# Sheet.net
KiCad netlist of a schematic drawn in Altium Designer
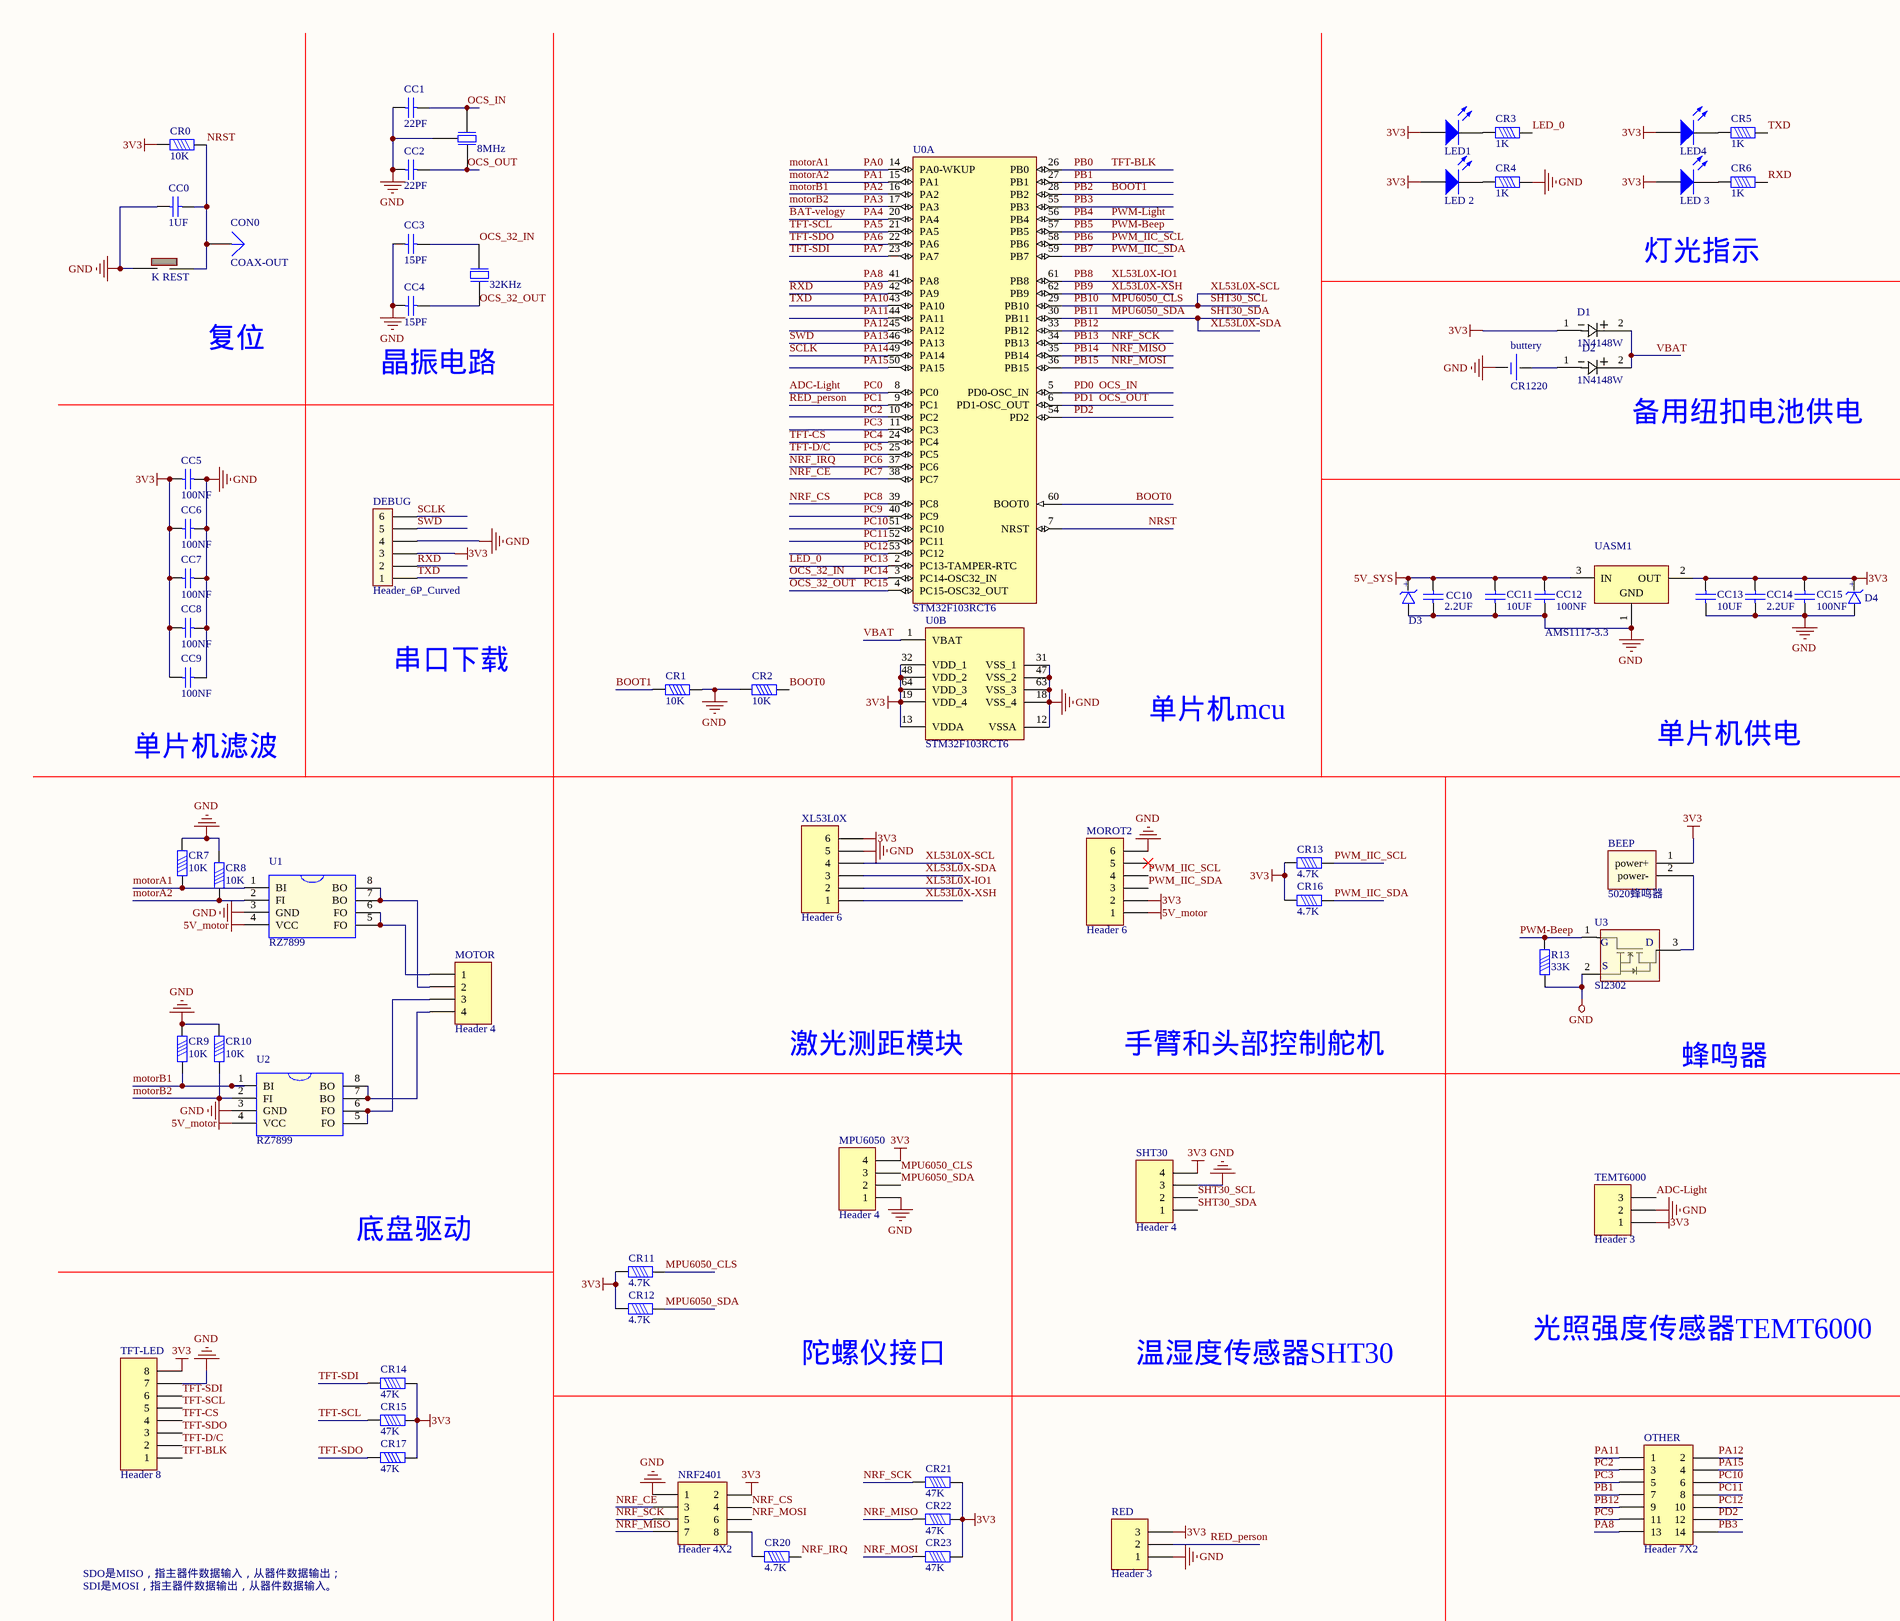
[diagram p0: Sheet.SchDoc, top left]
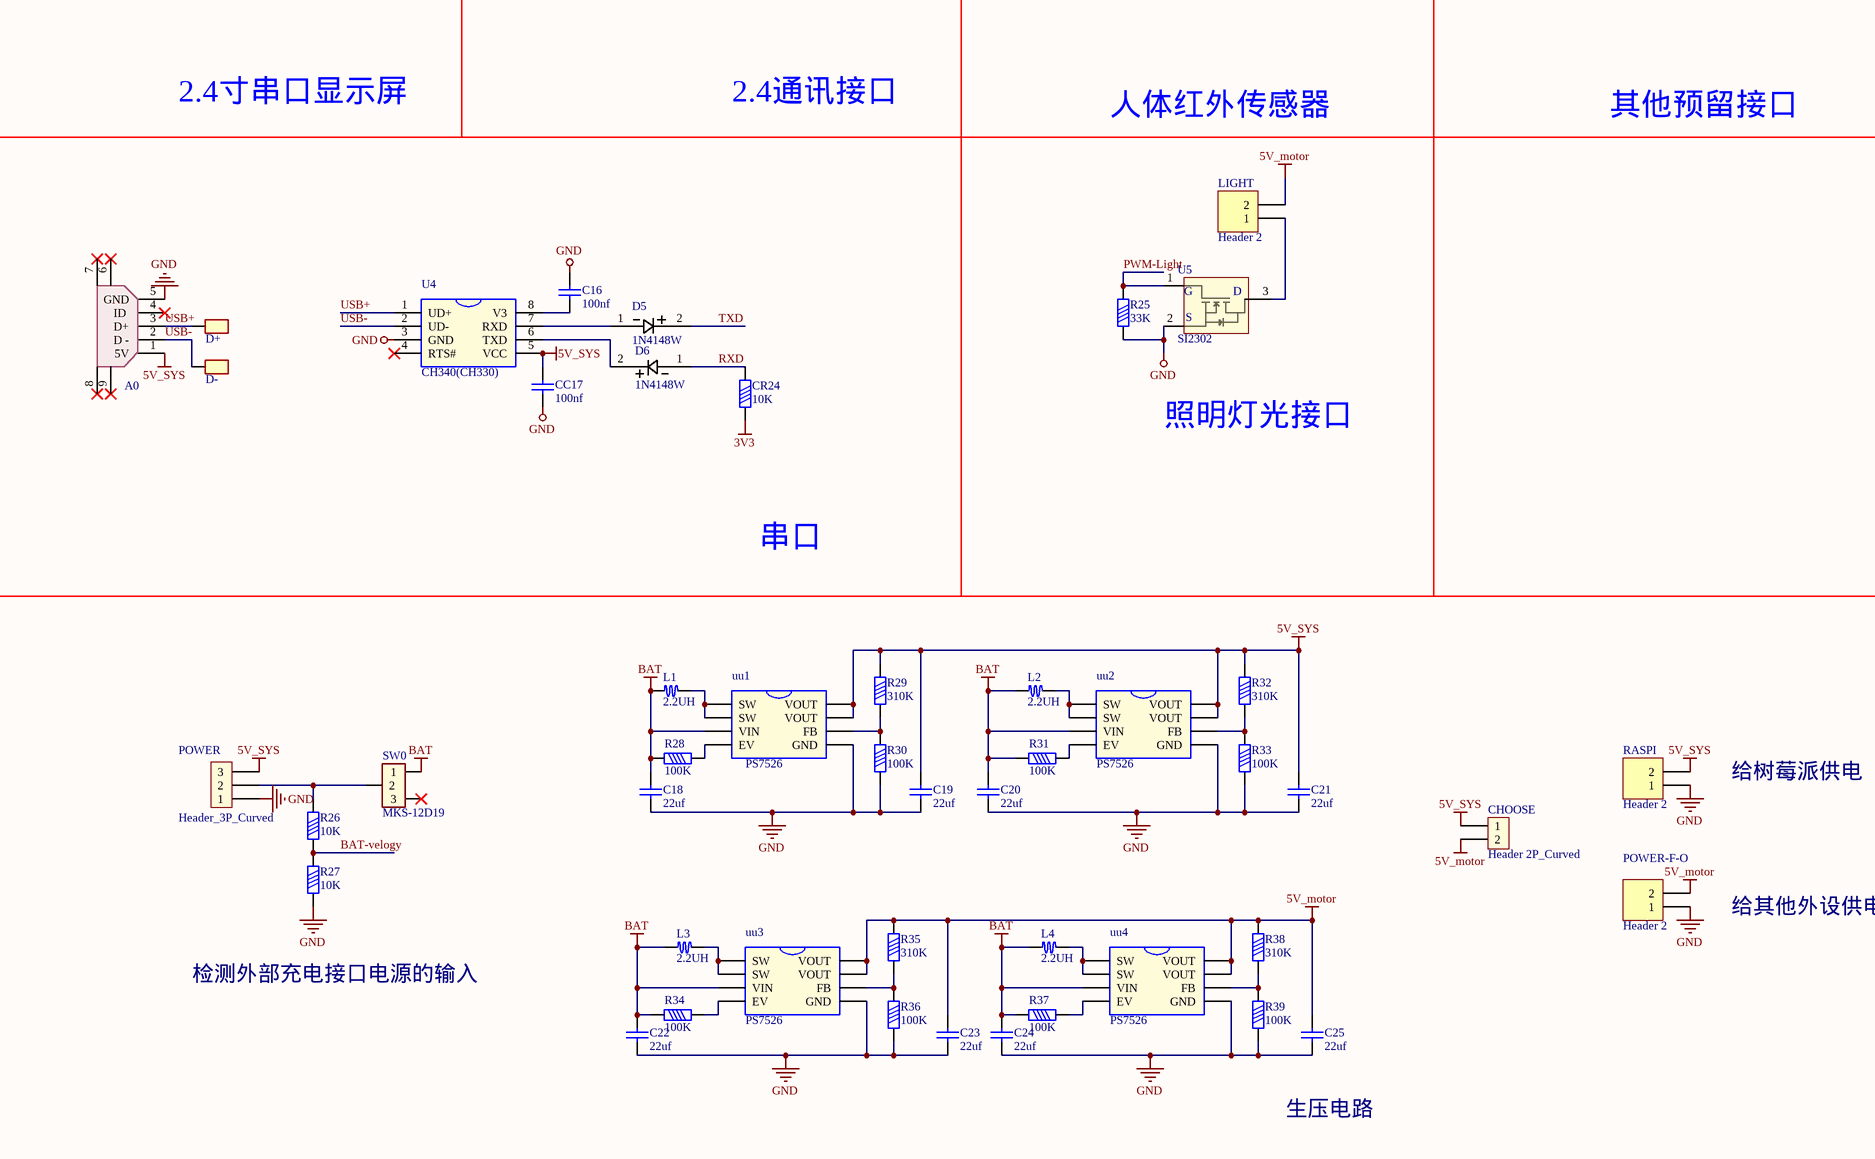
[diagram p1: Sheet.SchDoc, bottom left]

(export (version "E")
  (design (tool "Eeschema 10.0.6"))
  (components
    (comp (ref "8MHz")
      (value "XTAL 3225 8M")
      (footprint "T 3225")
      (libsource (lib "tianxiaohua_Schlib") (part "XTAL 3225 8M"))
    )
    (comp (ref "32KHz")
      (value "XTAL 3215 32.768kKHz")
      (footprint "T 3215")
      (libsource (lib "tianxiaohua_Schlib") (part "XTAL 3215 32.768kKHz"))
    )
    (comp (ref "A0")
      (value "Micro USB")
      (footprint "Micro USB")
      (libsource (lib "tianxiaohua_Schlib") (part "Micro USB"))
    )
    (comp (ref "BEEP")
      (value "5020蜂鸣器")
      (footprint "5020蜂鸣器")
      (description "蜂鸣器，贴片封装，长宽5.2mm")
      (libsource (lib "tianxiaohua_Schlib") (part "5020蜂鸣器"))
    )
    (comp (ref "buttery")
      (value "CR1220")
      (footprint "CR1220-buttery")
      (description "纽扣电池")
      (libsource (lib "tianxiaohua_Schlib") (part "CR1220"))
    )
    (comp (ref "C16")
      (value "100nf")
      (footprint "CC1608-0603")
      (description "Polarized Capacitor (Radial)")
      (fields (field (name "Comment") "Cap Chip 0603") (field (name "PUBLISHER") "Altium Limited"))
      (libsource (lib "EButterflyIntegratedLibrary") (part "Cap Chip 0603"))
    )
    (comp (ref "C18")
      (value "22uf")
      (footprint "CC2012-0805")
      (description "Polarized Capacitor (Radial)")
      (fields (field (name "Comment") "Cap Chip 0805") (field (name "PUBLISHER") "Altium Limited"))
      (libsource (lib "EButterflyIntegratedLibrary") (part "Cap Chip 0805"))
    )
    (comp (ref "C19")
      (value "22uf")
      (footprint "CC2012-0805")
      (description "Polarized Capacitor (Radial)")
      (fields (field (name "Comment") "Cap Chip 0805") (field (name "PUBLISHER") "Altium Limited"))
      (libsource (lib "EButterflyIntegratedLibrary") (part "Cap Chip 0805"))
    )
    (comp (ref "C20")
      (value "22uf")
      (footprint "CC2012-0805")
      (description "Polarized Capacitor (Radial)")
      (fields (field (name "Comment") "Cap Chip 0805") (field (name "PUBLISHER") "Altium Limited"))
      (libsource (lib "EButterflyIntegratedLibrary") (part "Cap Chip 0805"))
    )
    (comp (ref "C21")
      (value "22uf")
      (footprint "CC2012-0805")
      (description "Polarized Capacitor (Radial)")
      (fields (field (name "Comment") "Cap Chip 0805") (field (name "PUBLISHER") "Altium Limited"))
      (libsource (lib "EButterflyIntegratedLibrary") (part "Cap Chip 0805"))
    )
    (comp (ref "C22")
      (value "22uf")
      (footprint "CC2012-0805")
      (description "Polarized Capacitor (Radial)")
      (fields (field (name "Comment") "Cap Chip 0805") (field (name "PUBLISHER") "Altium Limited"))
      (libsource (lib "EButterflyIntegratedLibrary") (part "Cap Chip 0805"))
    )
    (comp (ref "C23")
      (value "22uf")
      (footprint "CC2012-0805")
      (description "Polarized Capacitor (Radial)")
      (fields (field (name "Comment") "Cap Chip 0805") (field (name "PUBLISHER") "Altium Limited"))
      (libsource (lib "EButterflyIntegratedLibrary") (part "Cap Chip 0805"))
    )
    (comp (ref "C24")
      (value "22uf")
      (footprint "CC2012-0805")
      (description "Polarized Capacitor (Radial)")
      (fields (field (name "Comment") "Cap Chip 0805") (field (name "PUBLISHER") "Altium Limited"))
      (libsource (lib "EButterflyIntegratedLibrary") (part "Cap Chip 0805"))
    )
    (comp (ref "C25")
      (value "22uf")
      (footprint "CC2012-0805")
      (description "Polarized Capacitor (Radial)")
      (fields (field (name "Comment") "Cap Chip 0805") (field (name "PUBLISHER") "Altium Limited"))
      (libsource (lib "EButterflyIntegratedLibrary") (part "Cap Chip 0805"))
    )
    (comp (ref "CC0")
      (value "1UF")
      (footprint "CC1608-0603")
      (description "Polarized Capacitor (Radial)")
      (fields (field (name "Comment") "Cap Chip 0603") (field (name "PUBLISHER") "Altium Limited"))
      (libsource (lib "EButterflyIntegratedLibrary") (part "Cap Chip 0603"))
    )
    (comp (ref "CC1")
      (value "22PF")
      (footprint "CC1608-0603")
      (description "Polarized Capacitor (Radial)")
      (fields (field (name "Comment") "Cap Chip 0603") (field (name "PUBLISHER") "Altium Limited"))
      (libsource (lib "EButterflyIntegratedLibrary") (part "Cap Chip 0603"))
    )
    (comp (ref "CC2")
      (value "22PF")
      (footprint "CC1608-0603")
      (description "Polarized Capacitor (Radial)")
      (fields (field (name "Comment") "Cap Chip 0603") (field (name "PUBLISHER") "Altium Limited"))
      (libsource (lib "EButterflyIntegratedLibrary") (part "Cap Chip 0603"))
    )
    (comp (ref "CC3")
      (value "15PF")
      (footprint "CC1608-0603")
      (description "Polarized Capacitor (Radial)")
      (fields (field (name "Comment") "Cap Chip 0603") (field (name "PUBLISHER") "Altium Limited"))
      (libsource (lib "EButterflyIntegratedLibrary") (part "Cap Chip 0603"))
    )
    (comp (ref "CC4")
      (value "15PF")
      (footprint "CC1608-0603")
      (description "Polarized Capacitor (Radial)")
      (fields (field (name "Comment") "Cap Chip 0603") (field (name "PUBLISHER") "Altium Limited"))
      (libsource (lib "EButterflyIntegratedLibrary") (part "Cap Chip 0603"))
    )
    (comp (ref "CC5")
      (value "100NF")
      (footprint "CC1608-0603")
      (description "Polarized Capacitor (Radial)")
      (fields (field (name "Comment") "Cap Chip 0603") (field (name "PUBLISHER") "Altium Limited"))
      (libsource (lib "EButterflyIntegratedLibrary") (part "Cap Chip 0603"))
    )
    (comp (ref "CC6")
      (value "100NF")
      (footprint "CC1608-0603")
      (description "Polarized Capacitor (Radial)")
      (fields (field (name "Comment") "Cap Chip 0603") (field (name "PUBLISHER") "Altium Limited"))
      (libsource (lib "EButterflyIntegratedLibrary") (part "Cap Chip 0603"))
    )
    (comp (ref "CC7")
      (value "100NF")
      (footprint "CC1608-0603")
      (description "Polarized Capacitor (Radial)")
      (fields (field (name "Comment") "Cap Chip 0603") (field (name "PUBLISHER") "Altium Limited"))
      (libsource (lib "EButterflyIntegratedLibrary") (part "Cap Chip 0603"))
    )
    (comp (ref "CC8")
      (value "100NF")
      (footprint "CC1608-0603")
      (description "Polarized Capacitor (Radial)")
      (fields (field (name "Comment") "Cap Chip 0603") (field (name "PUBLISHER") "Altium Limited"))
      (libsource (lib "EButterflyIntegratedLibrary") (part "Cap Chip 0603"))
    )
    (comp (ref "CC9")
      (value "100NF")
      (footprint "CC1608-0603")
      (description "Polarized Capacitor (Radial)")
      (fields (field (name "Comment") "Cap Chip 0603") (field (name "PUBLISHER") "Altium Limited"))
      (libsource (lib "EButterflyIntegratedLibrary") (part "Cap Chip 0603"))
    )
    (comp (ref "CC10")
      (value "2.2UF")
      (footprint "CC1608-0603")
      (description "Polarized Capacitor (Radial)")
      (fields (field (name "Comment") "Cap Chip 0603") (field (name "PUBLISHER") "Altium Limited"))
      (libsource (lib "EButterflyIntegratedLibrary") (part "Cap Chip 0603"))
    )
    (comp (ref "CC11")
      (value "10UF")
      (footprint "CC1608-0603")
      (description "Polarized Capacitor (Radial)")
      (fields (field (name "Comment") "Cap Chip 0603") (field (name "PUBLISHER") "Altium Limited"))
      (libsource (lib "EButterflyIntegratedLibrary") (part "Cap Chip 0603"))
    )
    (comp (ref "CC12")
      (value "100NF")
      (footprint "CC1608-0603")
      (description "Polarized Capacitor (Radial)")
      (fields (field (name "Comment") "Cap Chip 0603") (field (name "PUBLISHER") "Altium Limited"))
      (libsource (lib "EButterflyIntegratedLibrary") (part "Cap Chip 0603"))
    )
    (comp (ref "CC13")
      (value "10UF")
      (footprint "CC1608-0603")
      (description "Polarized Capacitor (Radial)")
      (fields (field (name "Comment") "Cap Chip 0603") (field (name "PUBLISHER") "Altium Limited"))
      (libsource (lib "EButterflyIntegratedLibrary") (part "Cap Chip 0603"))
    )
    (comp (ref "CC14")
      (value "2.2UF")
      (footprint "CC1608-0603")
      (description "Polarized Capacitor (Radial)")
      (fields (field (name "Comment") "Cap Chip 0603") (field (name "PUBLISHER") "Altium Limited"))
      (libsource (lib "EButterflyIntegratedLibrary") (part "Cap Chip 0603"))
    )
    (comp (ref "CC15")
      (value "100NF")
      (footprint "CC1608-0603")
      (description "Polarized Capacitor (Radial)")
      (fields (field (name "Comment") "Cap Chip 0603") (field (name "PUBLISHER") "Altium Limited"))
      (libsource (lib "EButterflyIntegratedLibrary") (part "Cap Chip 0603"))
    )
    (comp (ref "CC17")
      (value "100nf")
      (footprint "CC1608-0603")
      (description "Polarized Capacitor (Radial)")
      (fields (field (name "Comment") "Cap Chip 0603") (field (name "PUBLISHER") "Altium Limited"))
      (libsource (lib "EButterflyIntegratedLibrary") (part "Cap Chip 0603"))
    )
    (comp (ref "CHOOSE")
      (value "Header 2P_Curved")
      (footprint "Header_2_54_2PW")
      (description "弯的2P排针")
      (libsource (lib "tianxiaohua_Schlib") (part "Header 2P_Curved"))
    )
    (comp (ref "CON0")
      (value "COAX-OUT")
      (footprint "PIN1")
      (description "Coax-M Connector")
      (fields (field (name "PUBLISHER") "Altium Limited"))
      (libsource (lib "EButterflyIntegratedLibrary") (part "COAX-OUT"))
    )
    (comp (ref "CR0")
      (value "10K")
      (footprint "CR1608-0603")
      (description "Resistor")
      (fields (field (name "Comment") "Resistor Chip 0603") (field (name "PUBLISHER") "Altium Limited"))
      (libsource (lib "") (part "Resistor Chip 0603_1"))
    )
    (comp (ref "CR1")
      (value "10K")
      (footprint "CR1608-0603")
      (description "Resistor")
      (fields (field (name "Comment") "Resistor Chip 0603") (field (name "PUBLISHER") "Altium Limited"))
      (libsource (lib "") (part "Resistor Chip 0603_1"))
    )
    (comp (ref "CR2")
      (value "10K")
      (footprint "CR1608-0603")
      (description "Resistor")
      (fields (field (name "Comment") "Resistor Chip 0603") (field (name "PUBLISHER") "Altium Limited"))
      (libsource (lib "") (part "Resistor Chip 0603_1"))
    )
    (comp (ref "CR3")
      (value "1K")
      (footprint "CR1608-0603")
      (description "Resistor")
      (fields (field (name "Comment") "Resistor Chip 0603") (field (name "PUBLISHER") "Altium Limited"))
      (libsource (lib "") (part "Resistor Chip 0603_1"))
    )
    (comp (ref "CR4")
      (value "1K")
      (footprint "CR1608-0603")
      (description "Resistor")
      (fields (field (name "Comment") "Resistor Chip 0603") (field (name "PUBLISHER") "Altium Limited"))
      (libsource (lib "") (part "Resistor Chip 0603_1"))
    )
    (comp (ref "CR5")
      (value "1K")
      (footprint "CR1608-0603")
      (description "Resistor")
      (fields (field (name "Comment") "Resistor Chip 0603") (field (name "PUBLISHER") "Altium Limited"))
      (libsource (lib "") (part "Resistor Chip 0603_1"))
    )
    (comp (ref "CR6")
      (value "1K")
      (footprint "CR1608-0603")
      (description "Resistor")
      (fields (field (name "Comment") "Resistor Chip 0603") (field (name "PUBLISHER") "Altium Limited"))
      (libsource (lib "") (part "Resistor Chip 0603_1"))
    )
    (comp (ref "CR7")
      (value "10K")
      (footprint "CR1608-0603")
      (description "Resistor")
      (fields (field (name "Comment") "Resistor Chip 0603") (field (name "PUBLISHER") "Altium Limited"))
      (libsource (lib "") (part "Resistor Chip 0603_2"))
    )
    (comp (ref "CR8")
      (value "10K")
      (footprint "CR1608-0603")
      (description "Resistor")
      (fields (field (name "Comment") "Resistor Chip 0603") (field (name "PUBLISHER") "Altium Limited"))
      (libsource (lib "") (part "Resistor Chip 0603_2"))
    )
    (comp (ref "CR9")
      (value "10K")
      (footprint "CR1608-0603")
      (description "Resistor")
      (fields (field (name "Comment") "Resistor Chip 0603") (field (name "PUBLISHER") "Altium Limited"))
      (libsource (lib "EButterflyIntegratedLibrary") (part "Resistor Chip 0603"))
    )
    (comp (ref "CR10")
      (value "10K")
      (footprint "CR1608-0603")
      (description "Resistor")
      (fields (field (name "Comment") "Resistor Chip 0603") (field (name "PUBLISHER") "Altium Limited"))
      (libsource (lib "EButterflyIntegratedLibrary") (part "Resistor Chip 0603"))
    )
    (comp (ref "CR11")
      (value "4.7K")
      (footprint "CR1608-0603")
      (description "Resistor")
      (fields (field (name "Comment") "Resistor Chip 0603") (field (name "PUBLISHER") "Altium Limited"))
      (libsource (lib "") (part "Resistor Chip 0603_1"))
    )
    (comp (ref "CR12")
      (value "4.7K")
      (footprint "CR1608-0603")
      (description "Resistor")
      (fields (field (name "Comment") "Resistor Chip 0603") (field (name "PUBLISHER") "Altium Limited"))
      (libsource (lib "") (part "Resistor Chip 0603_1"))
    )
    (comp (ref "CR13")
      (value "4.7K")
      (footprint "CR1608-0603")
      (description "Resistor")
      (fields (field (name "Comment") "Resistor Chip 0603") (field (name "PUBLISHER") "Altium Limited"))
      (libsource (lib "") (part "Resistor Chip 0603_1"))
    )
    (comp (ref "CR14")
      (value "47K")
      (footprint "CR1608-0603")
      (description "Resistor")
      (fields (field (name "Comment") "Resistor Chip 0603") (field (name "PUBLISHER") "Altium Limited"))
      (libsource (lib "") (part "Resistor Chip 0603_1"))
    )
    (comp (ref "CR15")
      (value "47K")
      (footprint "CR1608-0603")
      (description "Resistor")
      (fields (field (name "Comment") "Resistor Chip 0603") (field (name "PUBLISHER") "Altium Limited"))
      (libsource (lib "") (part "Resistor Chip 0603_1"))
    )
    (comp (ref "CR16")
      (value "4.7K")
      (footprint "CR1608-0603")
      (description "Resistor")
      (fields (field (name "Comment") "Resistor Chip 0603") (field (name "PUBLISHER") "Altium Limited"))
      (libsource (lib "") (part "Resistor Chip 0603_1"))
    )
    (comp (ref "CR17")
      (value "47K")
      (footprint "CR1608-0603")
      (description "Resistor")
      (fields (field (name "Comment") "Resistor Chip 0603") (field (name "PUBLISHER") "Altium Limited"))
      (libsource (lib "") (part "Resistor Chip 0603_1"))
    )
    (comp (ref "CR20")
      (value "4.7K")
      (footprint "CR1608-0603")
      (description "Resistor")
      (fields (field (name "Comment") "Resistor Chip 0603") (field (name "PUBLISHER") "Altium Limited"))
      (libsource (lib "") (part "Resistor Chip 0603_1"))
    )
    (comp (ref "CR21")
      (value "47K")
      (footprint "CR1608-0603")
      (description "Resistor")
      (fields (field (name "Comment") "Resistor Chip 0603") (field (name "PUBLISHER") "Altium Limited"))
      (libsource (lib "") (part "Resistor Chip 0603_1"))
    )
    (comp (ref "CR22")
      (value "47K")
      (footprint "CR1608-0603")
      (description "Resistor")
      (fields (field (name "Comment") "Resistor Chip 0603") (field (name "PUBLISHER") "Altium Limited"))
      (libsource (lib "") (part "Resistor Chip 0603_1"))
    )
    (comp (ref "CR23")
      (value "47K")
      (footprint "CR1608-0603")
      (description "Resistor")
      (fields (field (name "Comment") "Resistor Chip 0603") (field (name "PUBLISHER") "Altium Limited"))
      (libsource (lib "") (part "Resistor Chip 0603_1"))
    )
    (comp (ref "CR24")
      (value "10K")
      (footprint "CR1608-0603")
      (description "Resistor")
      (fields (field (name "Comment") "Resistor Chip 0603") (field (name "PUBLISHER") "Altium Limited"))
      (libsource (lib "") (part "Resistor Chip 0603_2"))
    )
    (comp (ref "D+")
      (value "H0")
      (footprint "header 1")
      (libsource (lib "tianxiaohua_Schlib") (part "header 1"))
    )
    (comp (ref "D-")
      (value "H0")
      (footprint "header 1")
      (libsource (lib "tianxiaohua_Schlib") (part "header 1"))
    )
    (comp (ref "D1")
      (value "1N4148W")
      (footprint "SOD-123")
      (description "开关二极管 贴片 1N4148W 1206/SOD-123 丝印T4 150MA 75V")
      (libsource (lib "tianxiaohua_Schlib") (part "1N4148W"))
    )
    (comp (ref "D2")
      (value "1N4148W")
      (footprint "SOD-123")
      (description "开关二极管 贴片 1N4148W 1206/SOD-123 丝印T4 150MA 75V")
      (libsource (lib "tianxiaohua_Schlib") (part "1N4148W"))
    )
    (comp (ref "D3")
      (value "SMBJ3.3A")
      (footprint "DO214AA(SMB)")
      (description "3.3V稳压管，缓解瞬间电压冲击")
      (libsource (lib "tianxiaohua_Schlib") (part "SMBJ3.3A"))
    )
    (comp (ref "D4")
      (value "SMBJ3.3A")
      (footprint "DO214AA(SMB)")
      (description "3.3V稳压管，缓解瞬间电压冲击")
      (libsource (lib "tianxiaohua_Schlib") (part "SMBJ3.3A"))
    )
    (comp (ref "D5")
      (value "1N4148W")
      (footprint "SOD-123")
      (description "开关二极管 贴片 1N4148W 1206/SOD-123 丝印T4 150MA 75V")
      (libsource (lib "tianxiaohua_Schlib") (part "1N4148W"))
    )
    (comp (ref "D6")
      (value "1N4148W")
      (footprint "SOD-123")
      (description "开关二极管 贴片 1N4148W 1206/SOD-123 丝印T4 150MA 75V")
      (libsource (lib "tianxiaohua_Schlib") (part "1N4148W"))
    )
    (comp (ref "DEBUG")
      (value "Header_6P_Curved")
      (footprint "Header_2_54_6PW")
      (description "弯的6P排针")
      (libsource (lib "tianxiaohua_Schlib") (part "Header_6P_Curved"))
    )
    (comp (ref "K REST")
      (value "KEY 3*4")
      (footprint "KEY 3*4")
      (libsource (lib "tianxiaohua_Schlib") (part "KEY 3*4"))
    )
    (comp (ref "L1")
      (value "2.2UH")
      (footprint "Inductor-1040")
      (description "圆柱线圈的贴片电感")
      (libsource (lib "tianxiaohua_Schlib") (part "Inductor"))
    )
    (comp (ref "L2")
      (value "2.2UH")
      (footprint "Inductor-1040")
      (description "圆柱线圈的贴片电感")
      (libsource (lib "tianxiaohua_Schlib") (part "Inductor"))
    )
    (comp (ref "L3")
      (value "2.2UH")
      (footprint "Inductor-1040")
      (description "圆柱线圈的贴片电感")
      (libsource (lib "tianxiaohua_Schlib") (part "Inductor"))
    )
    (comp (ref "L4")
      (value "2.2UH")
      (footprint "Inductor-1040")
      (description "圆柱线圈的贴片电感")
      (libsource (lib "tianxiaohua_Schlib") (part "Inductor"))
    )
    (comp (ref "LED 2")
      (value "LED Chip")
      (footprint "CLED1608-0603")
      (description "Typical Chip LED")
      (fields (field (name "PUBLISHER") "Altium Limited"))
      (libsource (lib "EButterflyIntegratedLibrary") (part "LED Chip"))
    )
    (comp (ref "LED 3")
      (value "LED Chip")
      (footprint "CLED1608-0603")
      (description "Typical Chip LED")
      (fields (field (name "PUBLISHER") "Altium Limited"))
      (libsource (lib "EButterflyIntegratedLibrary") (part "LED Chip"))
    )
    (comp (ref "LED1")
      (value "LED Chip")
      (footprint "CLED1608-0603")
      (description "Typical Chip LED")
      (fields (field (name "PUBLISHER") "Altium Limited"))
      (libsource (lib "EButterflyIntegratedLibrary") (part "LED Chip"))
    )
    (comp (ref "LED4")
      (value "LED Chip")
      (footprint "CLED1608-0603")
      (description "Typical Chip LED")
      (fields (field (name "PUBLISHER") "Altium Limited"))
      (libsource (lib "EButterflyIntegratedLibrary") (part "LED Chip"))
    )
    (comp (ref "LIGHT")
      (value "Header 2")
      (footprint "HX2.54-2")
      (description "Header, 2-Pin")
      (fields (field (name "PUBLISHER") "Altium Limited"))
      (libsource (lib "EButterflyIntegratedLibrary") (part "Header 2"))
    )
    (comp (ref "MOROT2")
      (value "Header 6")
      (footprint "HX2.54-6")
      (description "Header, 6-Pin")
      (fields (field (name "PUBLISHER") "Altium Limited"))
      (libsource (lib "EButterflyIntegratedLibrary") (part "Header 6"))
    )
    (comp (ref "MOTOR")
      (value "Header 4")
      (footprint "HX2.54-4")
      (description "Header, 4-Pin")
      (fields (field (name "PUBLISHER") "Altium Limited"))
      (libsource (lib "") (part "Header 4_1"))
    )
    (comp (ref "MPU6050")
      (value "Header 4")
      (footprint "HX2.54-4")
      (description "Header, 4-Pin")
      (fields (field (name "PUBLISHER") "Altium Limited"))
      (libsource (lib "EButterflyIntegratedLibrary") (part "Header 4"))
    )
    (comp (ref "NRF2401")
      (value "Header 4X2")
      (footprint "HDR2X4")
      (description "Header, 4-Pin, Dual row")
      (fields (field (name "PUBLISHER") "Altium Limited"))
      (libsource (lib "EButterflyIntegratedLibrary") (part "Header 4X2"))
    )
    (comp (ref "OTHER")
      (value "Header 7X2")
      (footprint "HDR2X7")
      (description "Header, 7-Pin, Dual row")
      (fields (field (name "PUBLISHER") "Altium Limited"))
      (libsource (lib "EButterflyIntegratedLibrary") (part "Header 7X2"))
    )
    (comp (ref "POWER")
      (value "Header_3P_Curved")
      (footprint "Header_2_54_3PW")
      (description "弯的3P排针")
      (libsource (lib "tianxiaohua_Schlib") (part "Header_3P_Curved"))
    )
    (comp (ref "POWER-F-O")
      (value "Header 2")
      (footprint "HX2.54-2")
      (description "Header, 2-Pin")
      (fields (field (name "PUBLISHER") "Altium Limited"))
      (libsource (lib "EButterflyIntegratedLibrary") (part "Header 2"))
    )
    (comp (ref "R13")
      (value "33K")
      (footprint "CR1608-0603")
      (description "Resistor")
      (fields (field (name "Comment") "Resistor Chip 0603") (field (name "PUBLISHER") "Altium Limited"))
      (libsource (lib "") (part "Resistor Chip 0603_2"))
    )
    (comp (ref "R25")
      (value "33K")
      (footprint "CR1608-0603")
      (description "Resistor")
      (fields (field (name "Comment") "Resistor Chip 0603") (field (name "PUBLISHER") "Altium Limited"))
      (libsource (lib "") (part "Resistor Chip 0603_2"))
    )
    (comp (ref "R26")
      (value "10K")
      (footprint "CR1608-0603")
      (description "Resistor")
      (fields (field (name "Comment") "Resistor Chip 0603") (field (name "PUBLISHER") "Altium Limited"))
      (libsource (lib "") (part "Resistor Chip 0603_2"))
    )
    (comp (ref "R27")
      (value "10K")
      (footprint "CR1608-0603")
      (description "Resistor")
      (fields (field (name "Comment") "Resistor Chip 0603") (field (name "PUBLISHER") "Altium Limited"))
      (libsource (lib "EButterflyIntegratedLibrary") (part "Resistor Chip 0603"))
    )
    (comp (ref "R28")
      (value "100K")
      (footprint "CR1608-0603")
      (description "Resistor")
      (fields (field (name "Comment") "Resistor Chip 0603") (field (name "PUBLISHER") "Altium Limited"))
      (libsource (lib "") (part "Resistor Chip 0603_1"))
    )
    (comp (ref "R29")
      (value "310K")
      (footprint "CR1608-0603")
      (description "Resistor")
      (fields (field (name "Comment") "Resistor Chip 0603") (field (name "PUBLISHER") "Altium Limited"))
      (libsource (lib "EButterflyIntegratedLibrary") (part "Resistor Chip 0603"))
    )
    (comp (ref "R30")
      (value "100K")
      (footprint "CR1608-0603")
      (description "Resistor")
      (fields (field (name "Comment") "Resistor Chip 0603") (field (name "PUBLISHER") "Altium Limited"))
      (libsource (lib "EButterflyIntegratedLibrary") (part "Resistor Chip 0603"))
    )
    (comp (ref "R31")
      (value "100K")
      (footprint "CR1608-0603")
      (description "Resistor")
      (fields (field (name "Comment") "Resistor Chip 0603") (field (name "PUBLISHER") "Altium Limited"))
      (libsource (lib "") (part "Resistor Chip 0603_1"))
    )
    (comp (ref "R32")
      (value "310K")
      (footprint "CR1608-0603")
      (description "Resistor")
      (fields (field (name "Comment") "Resistor Chip 0603") (field (name "PUBLISHER") "Altium Limited"))
      (libsource (lib "EButterflyIntegratedLibrary") (part "Resistor Chip 0603"))
    )
    (comp (ref "R33")
      (value "100K")
      (footprint "CR1608-0603")
      (description "Resistor")
      (fields (field (name "Comment") "Resistor Chip 0603") (field (name "PUBLISHER") "Altium Limited"))
      (libsource (lib "EButterflyIntegratedLibrary") (part "Resistor Chip 0603"))
    )
    (comp (ref "R34")
      (value "100K")
      (footprint "CR1608-0603")
      (description "Resistor")
      (fields (field (name "Comment") "Resistor Chip 0603") (field (name "PUBLISHER") "Altium Limited"))
      (libsource (lib "") (part "Resistor Chip 0603_1"))
    )
    (comp (ref "R35")
      (value "310K")
      (footprint "CR1608-0603")
      (description "Resistor")
      (fields (field (name "Comment") "Resistor Chip 0603") (field (name "PUBLISHER") "Altium Limited"))
      (libsource (lib "EButterflyIntegratedLibrary") (part "Resistor Chip 0603"))
    )
    (comp (ref "R36")
      (value "100K")
      (footprint "CR1608-0603")
      (description "Resistor")
      (fields (field (name "Comment") "Resistor Chip 0603") (field (name "PUBLISHER") "Altium Limited"))
      (libsource (lib "EButterflyIntegratedLibrary") (part "Resistor Chip 0603"))
    )
    (comp (ref "R37")
      (value "100K")
      (footprint "CR1608-0603")
      (description "Resistor")
      (fields (field (name "Comment") "Resistor Chip 0603") (field (name "PUBLISHER") "Altium Limited"))
      (libsource (lib "") (part "Resistor Chip 0603_1"))
    )
    (comp (ref "R38")
      (value "310K")
      (footprint "CR1608-0603")
      (description "Resistor")
      (fields (field (name "Comment") "Resistor Chip 0603") (field (name "PUBLISHER") "Altium Limited"))
      (libsource (lib "EButterflyIntegratedLibrary") (part "Resistor Chip 0603"))
    )
    (comp (ref "R39")
      (value "100K")
      (footprint "CR1608-0603")
      (description "Resistor")
      (fields (field (name "Comment") "Resistor Chip 0603") (field (name "PUBLISHER") "Altium Limited"))
      (libsource (lib "EButterflyIntegratedLibrary") (part "Resistor Chip 0603"))
    )
    (comp (ref "RASPI")
      (value "Header 2")
      (footprint "HX2.54-2")
      (description "Header, 2-Pin")
      (fields (field (name "PUBLISHER") "Altium Limited"))
      (libsource (lib "EButterflyIntegratedLibrary") (part "Header 2"))
    )
    (comp (ref "RED")
      (value "Header 3")
      (footprint "HX2.54-3")
      (description "Header, 3-Pin")
      (fields (field (name "PUBLISHER") "Altium Limited"))
      (libsource (lib "EButterflyIntegratedLibrary") (part "Header 3"))
    )
    (comp (ref "SHT30")
      (value "Header 4")
      (footprint "HX2.54-4")
      (description "Header, 4-Pin")
      (fields (field (name "PUBLISHER") "Altium Limited"))
      (libsource (lib "EButterflyIntegratedLibrary") (part "Header 4"))
    )
    (comp (ref "SW0")
      (value "MKS-12D19")
      (footprint "SW  MKS 12D19")
      (libsource (lib "tianxiaohua_Schlib") (part "sw-MSK-12D19"))
    )
    (comp (ref "TEMT6000")
      (value "Header 3")
      (footprint "HX2.54-3")
      (description "Header, 3-Pin")
      (fields (field (name "PUBLISHER") "Altium Limited"))
      (libsource (lib "EButterflyIntegratedLibrary") (part "Header 3"))
    )
    (comp (ref "TFT-LED")
      (value "Header 8")
      (footprint "HX2.54-8")
      (description "Header, 8-Pin")
      (fields (field (name "PUBLISHER") "Altium Limited"))
      (libsource (lib "EButterflyIntegratedLibrary") (part "Header 8"))
    )
    (comp (ref "U0")
      (value "STM32F103RCT6")
      (footprint "STM-LQFP64_N")
      (libsource (lib "STMicroelectronics STM32 F1") (part "STM32F103RCT6"))
    )
    (comp (ref "U1")
      (value "RZ7899")
      (footprint "SOP8")
      (description "电机驱动:输入支持3V-25V，输出支持6A")
      (libsource (lib "tianxiaohua_Schlib") (part "RZ7899"))
    )
    (comp (ref "U2")
      (value "RZ7899")
      (footprint "SOP8")
      (description "电机驱动:输入支持3V-25V，输出支持6A")
      (libsource (lib "tianxiaohua_Schlib") (part "RZ7899"))
    )
    (comp (ref "U3")
      (value "SI2302")
      (footprint "SOT-23 SI2302")
      (description "NMOS场效应MOS管 SOT-23")
      (libsource (lib "tianxiaohua_Schlib") (part "SI2302"))
    )
    (comp (ref "U4")
      (value "CH340(CH330)")
      (footprint "SOP8")
      (description "USB转串口rs232的芯片，内置晶振")
      (libsource (lib "tianxiaohua_Schlib") (part "CH340(CH330)"))
    )
    (comp (ref "U5")
      (value "SI2302")
      (footprint "SOT-23 SI2302")
      (description "NMOS场效应MOS管 SOT-23")
      (libsource (lib "tianxiaohua_Schlib") (part "SI2302"))
    )
    (comp (ref "UASM1")
      (value "AMS1117-3.3")
      (footprint "SOT-223")
      (description "POSITIVE OUTPUT VOLTAGE")
      (libsource (lib "EButterflyIntegratedLibrary") (part "AMS1117"))
    )
    (comp (ref "uu1")
      (value "PS7526")
      (footprint "ESOP8")
      (libsource (lib "tianxiaohua_Schlib") (part "PS7526"))
    )
    (comp (ref "uu2")
      (value "PS7526")
      (footprint "ESOP8")
      (libsource (lib "tianxiaohua_Schlib") (part "PS7526"))
    )
    (comp (ref "uu3")
      (value "PS7526")
      (footprint "ESOP8")
      (libsource (lib "tianxiaohua_Schlib") (part "PS7526"))
    )
    (comp (ref "uu4")
      (value "PS7526")
      (footprint "ESOP8")
      (libsource (lib "tianxiaohua_Schlib") (part "PS7526"))
    )
    (comp (ref "XL53L0X")
      (value "Header 6")
      (footprint "HX2.54-6")
      (description "Header, 6-Pin")
      (fields (field (name "PUBLISHER") "Altium Limited"))
      (libsource (lib "EButterflyIntegratedLibrary") (part "Header 6"))
    )
  )
  (nets
    (net (code "1") (name "/ADC-Light") (class "Default")
      (node (ref "TEMT6000") (pin "3") (pinfunction "3_3") (pintype "passive"))
      (node (ref "U0") (pin "8") (pinfunction "PC0_8") (pintype "bidirectional"))
    )
    (net (code "2") (name "/BAT-velogy") (class "Default")
      (node (ref "R26") (pin "1") (pinfunction "1_1") (pintype "passive"))
      (node (ref "R27") (pin "1") (pinfunction "1_1") (pintype "passive"))
      (node (ref "U0") (pin "20") (pinfunction "PA4_20") (pintype "bidirectional"))
    )
    (net (code "3") (name "/BOOT0") (class "Default")
      (node (ref "CR2") (pin "2") (pinfunction "2_2") (pintype "passive"))
      (node (ref "U0") (pin "60") (pinfunction "BOOT0_60") (pintype "input"))
    )
    (net (code "4") (name "/BOOT1") (class "Default")
      (node (ref "CR1") (pin "1") (pinfunction "1_1") (pintype "passive"))
      (node (ref "U0") (pin "28") (pinfunction "PB2_28") (pintype "bidirectional"))
    )
    (net (code "5") (name "/LED_0") (class "Default")
      (node (ref "CR3") (pin "2") (pinfunction "2_2") (pintype "passive"))
      (node (ref "U0") (pin "2") (pinfunction "PC13-TAMPER-RTC_2") (pintype "bidirectional"))
    )
    (net (code "6") (name "/MPU6050_CLS") (class "Default")
      (node (ref "CR11") (pin "2") (pinfunction "2_2") (pintype "passive"))
      (node (ref "MPU6050") (pin "3") (pinfunction "3_3") (pintype "passive"))
      (node (ref "SHT30") (pin "2") (pinfunction "2_2") (pintype "passive"))
      (node (ref "U0") (pin "29") (pinfunction "PB10_29") (pintype "bidirectional"))
      (node (ref "XL53L0X") (pin "4") (pinfunction "4_4") (pintype "passive"))
    )
    (net (code "7") (name "/MPU6050_SDA") (class "Default")
      (node (ref "CR12") (pin "2") (pinfunction "2_2") (pintype "passive"))
      (node (ref "MPU6050") (pin "2") (pinfunction "2_2") (pintype "passive"))
      (node (ref "SHT30") (pin "1") (pinfunction "1_1") (pintype "passive"))
      (node (ref "U0") (pin "30") (pinfunction "PB11_30") (pintype "bidirectional"))
      (node (ref "XL53L0X") (pin "3") (pinfunction "3_3") (pintype "passive"))
    )
    (net (code "8") (name "/NRF_CE") (class "Default")
      (node (ref "NRF2401") (pin "3") (pinfunction "3_3") (pintype "passive"))
      (node (ref "U0") (pin "38") (pinfunction "PC7_38") (pintype "bidirectional"))
    )
    (net (code "9") (name "/NRF_CS") (class "Default")
      (node (ref "NRF2401") (pin "4") (pinfunction "4_4") (pintype "passive"))
      (node (ref "U0") (pin "39") (pinfunction "PC8_39") (pintype "bidirectional"))
    )
    (net (code "10") (name "/NRF_IRQ") (class "Default")
      (node (ref "CR20") (pin "2") (pinfunction "2_2") (pintype "passive"))
      (node (ref "U0") (pin "37") (pinfunction "PC6_37") (pintype "bidirectional"))
    )
    (net (code "11") (name "/NRF_MISO") (class "Default")
      (node (ref "CR22") (pin "1") (pinfunction "1_1") (pintype "passive"))
      (node (ref "NRF2401") (pin "7") (pinfunction "7_7") (pintype "passive"))
      (node (ref "U0") (pin "35") (pinfunction "PB14_35") (pintype "bidirectional"))
    )
    (net (code "12") (name "/NRF_MOSI") (class "Default")
      (node (ref "CR23") (pin "1") (pinfunction "1_1") (pintype "passive"))
      (node (ref "NRF2401") (pin "6") (pinfunction "6_6") (pintype "passive"))
      (node (ref "U0") (pin "36") (pinfunction "PB15_36") (pintype "bidirectional"))
    )
    (net (code "13") (name "/NRF_SCK") (class "Default")
      (node (ref "CR21") (pin "1") (pinfunction "1_1") (pintype "passive"))
      (node (ref "NRF2401") (pin "5") (pinfunction "5_5") (pintype "passive"))
      (node (ref "U0") (pin "34") (pinfunction "PB13_34") (pintype "bidirectional"))
    )
    (net (code "14") (name "/NRST") (class "Default")
      (node (ref "CC0") (pin "2") (pinfunction "2_2") (pintype "passive"))
      (node (ref "CON0") (pin "1") (pinfunction "A_1") (pintype "passive"))
      (node (ref "CR0") (pin "2") (pinfunction "2_2") (pintype "passive"))
      (node (ref "K REST") (pin "2") (pinfunction "2_2") (pintype "passive"))
      (node (ref "U0") (pin "7") (pinfunction "NRST_7") (pintype "bidirectional"))
    )
    (net (code "15") (name "/OCS_32_IN") (class "Default")
      (node (ref "32KHz") (pin "2") (pinfunction "OSC2_2") (pintype "passive"))
      (node (ref "CC3") (pin "2") (pinfunction "2_2") (pintype "passive"))
      (node (ref "U0") (pin "3") (pinfunction "PC14-OSC32_IN_3") (pintype "bidirectional"))
    )
    (net (code "16") (name "/OCS_32_OUT") (class "Default")
      (node (ref "32KHz") (pin "1") (pinfunction "OSC1_1") (pintype "passive"))
      (node (ref "CC4") (pin "2") (pinfunction "2_2") (pintype "passive"))
      (node (ref "U0") (pin "4") (pinfunction "PC15-OSC32_OUT_4") (pintype "bidirectional"))
    )
    (net (code "17") (name "/OCS_IN") (class "Default")
      (node (ref "8MHz") (pin "1") (pinfunction "OSC1_1") (pintype "passive"))
      (node (ref "CC1") (pin "2") (pinfunction "2_2") (pintype "passive"))
      (node (ref "U0") (pin "5") (pinfunction "PD0-OSC_IN_5") (pintype "bidirectional"))
    )
    (net (code "18") (name "/OCS_OUT") (class "Default")
      (node (ref "8MHz") (pin "2") (pinfunction "OSC2_2") (pintype "passive"))
      (node (ref "CC2") (pin "2") (pinfunction "2_2") (pintype "passive"))
      (node (ref "U0") (pin "6") (pinfunction "PD1-OSC_OUT_6") (pintype "bidirectional"))
    )
    (net (code "19") (name "/PA0") (class "Default")
      (node (ref "CR7") (pin "1") (pinfunction "1_1") (pintype "passive"))
      (node (ref "U0") (pin "14") (pinfunction "PA0-WKUP_14") (pintype "bidirectional"))
      (node (ref "U1") (pin "1") (pinfunction "BI_1") (pintype "passive"))
    )
    (net (code "20") (name "/PA1") (class "Default")
      (node (ref "CR8") (pin "1") (pinfunction "1_1") (pintype "passive"))
      (node (ref "U0") (pin "15") (pinfunction "PA1_15") (pintype "bidirectional"))
      (node (ref "U1") (pin "2") (pinfunction "FI_2") (pintype "passive"))
    )
    (net (code "21") (name "/PA2") (class "Default")
      (node (ref "CR9") (pin "2") (pinfunction "2_2") (pintype "passive"))
      (node (ref "U0") (pin "16") (pinfunction "PA2_16") (pintype "bidirectional"))
      (node (ref "U2") (pin "1") (pinfunction "BI_1") (pintype "passive"))
    )
    (net (code "22") (name "/PA3") (class "Default")
      (node (ref "CR10") (pin "2") (pinfunction "2_2") (pintype "passive"))
      (node (ref "U0") (pin "17") (pinfunction "PA3_17") (pintype "bidirectional"))
      (node (ref "U2") (pin "2") (pinfunction "FI_2") (pintype "passive"))
    )
    (net (code "23") (name "/PA5") (class "Default")
      (node (ref "CR15") (pin "1") (pinfunction "1_1") (pintype "passive"))
      (node (ref "TFT-LED") (pin "5") (pinfunction "5_5") (pintype "passive"))
      (node (ref "U0") (pin "21") (pinfunction "PA5_21") (pintype "bidirectional"))
    )
    (net (code "24") (name "/PA6") (class "Default")
      (node (ref "CR17") (pin "1") (pinfunction "1_1") (pintype "passive"))
      (node (ref "TFT-LED") (pin "3") (pinfunction "3_3") (pintype "passive"))
      (node (ref "U0") (pin "22") (pinfunction "PA6_22") (pintype "bidirectional"))
    )
    (net (code "25") (name "/PA7") (class "Default")
      (node (ref "CR14") (pin "1") (pinfunction "1_1") (pintype "passive"))
      (node (ref "TFT-LED") (pin "6") (pinfunction "6_6") (pintype "passive"))
      (node (ref "U0") (pin "23") (pinfunction "PA7_23") (pintype "bidirectional"))
    )
    (net (code "26") (name "/PA8") (class "Default")
      (node (ref "OTHER") (pin "13") (pinfunction "13_13") (pintype "passive"))
      (node (ref "U0") (pin "41") (pinfunction "PA8_41") (pintype "bidirectional"))
    )
    (net (code "27") (name "/PA9") (class "Default")
      (node (ref "CR24") (pin "2") (pinfunction "2_2") (pintype "passive"))
      (node (ref "CR6") (pin "2") (pinfunction "2_2") (pintype "passive"))
      (node (ref "D6") (pin "1") (pinfunction "1_1") (pintype "passive"))
      (node (ref "DEBUG") (pin "2") (pinfunction "2_2") (pintype "passive"))
      (node (ref "U0") (pin "42") (pinfunction "PA9_42") (pintype "bidirectional"))
    )
    (net (code "28") (name "/PA10") (class "Default")
      (node (ref "CR5") (pin "2") (pinfunction "2_2") (pintype "passive"))
      (node (ref "D5") (pin "2") (pinfunction "2_2") (pintype "passive"))
      (node (ref "DEBUG") (pin "1") (pinfunction "1_1") (pintype "passive"))
      (node (ref "U0") (pin "43") (pinfunction "PA10_43") (pintype "bidirectional"))
    )
    (net (code "29") (name "/PA11") (class "Default")
      (node (ref "OTHER") (pin "1") (pinfunction "1_1") (pintype "passive"))
      (node (ref "U0") (pin "44") (pinfunction "PA11_44") (pintype "bidirectional"))
    )
    (net (code "30") (name "/PA12") (class "Default")
      (node (ref "OTHER") (pin "2") (pinfunction "2_2") (pintype "passive"))
      (node (ref "U0") (pin "45") (pinfunction "PA12_45") (pintype "bidirectional"))
    )
    (net (code "31") (name "/PA13") (class "Default")
      (node (ref "DEBUG") (pin "5") (pinfunction "5_5") (pintype "passive"))
      (node (ref "U0") (pin "46") (pinfunction "PA13_46") (pintype "bidirectional"))
    )
    (net (code "32") (name "/PA14") (class "Default")
      (node (ref "DEBUG") (pin "6") (pinfunction "6_6") (pintype "passive"))
      (node (ref "U0") (pin "49") (pinfunction "PA14_49") (pintype "bidirectional"))
    )
    (net (code "33") (name "/PA15") (class "Default")
      (node (ref "OTHER") (pin "4") (pinfunction "4_4") (pintype "passive"))
      (node (ref "U0") (pin "50") (pinfunction "PA15_50") (pintype "bidirectional"))
    )
    (net (code "34") (name "/PB0") (class "Default")
      (node (ref "TFT-LED") (pin "1") (pinfunction "1_1") (pintype "passive"))
      (node (ref "U0") (pin "26") (pinfunction "PB0_26") (pintype "bidirectional"))
    )
    (net (code "35") (name "/PB1") (class "Default")
      (node (ref "OTHER") (pin "7") (pinfunction "7_7") (pintype "passive"))
      (node (ref "U0") (pin "27") (pinfunction "PB1_27") (pintype "bidirectional"))
    )
    (net (code "36") (name "/PB3") (class "Default")
      (node (ref "OTHER") (pin "14") (pinfunction "14_14") (pintype "passive"))
      (node (ref "U0") (pin "55") (pinfunction "PB3_55") (pintype "bidirectional"))
    )
    (net (code "37") (name "/PB4") (class "Default")
      (node (ref "R25") (pin "2") (pinfunction "2_2") (pintype "passive"))
      (node (ref "U0") (pin "56") (pinfunction "PB4_56") (pintype "bidirectional"))
      (node (ref "U5") (pin "1") (pinfunction "GATE_1") (pintype "passive"))
    )
    (net (code "38") (name "/PB5") (class "Default")
      (node (ref "R13") (pin "2") (pinfunction "2_2") (pintype "passive"))
      (node (ref "U0") (pin "57") (pinfunction "PB5_57") (pintype "bidirectional"))
      (node (ref "U3") (pin "1") (pinfunction "GATE_1") (pintype "passive"))
    )
    (net (code "39") (name "/PB6") (class "Default")
      (node (ref "CR13") (pin "2") (pinfunction "2_2") (pintype "passive"))
      (node (ref "MOROT2") (pin "4") (pinfunction "4_4") (pintype "passive"))
      (node (ref "U0") (pin "58") (pinfunction "PB6_58") (pintype "bidirectional"))
    )
    (net (code "40") (name "/PB7") (class "Default")
      (node (ref "CR16") (pin "2") (pinfunction "2_2") (pintype "passive"))
      (node (ref "MOROT2") (pin "3") (pinfunction "3_3") (pintype "passive"))
      (node (ref "U0") (pin "59") (pinfunction "PB7_59") (pintype "bidirectional"))
    )
    (net (code "41") (name "/PB8") (class "Default")
      (node (ref "U0") (pin "61") (pinfunction "PB8_61") (pintype "bidirectional"))
      (node (ref "XL53L0X") (pin "2") (pinfunction "2_2") (pintype "passive"))
    )
    (net (code "42") (name "/PB9") (class "Default")
      (node (ref "U0") (pin "62") (pinfunction "PB9_62") (pintype "bidirectional"))
      (node (ref "XL53L0X") (pin "1") (pinfunction "1_1") (pintype "passive"))
    )
    (net (code "43") (name "/PB12") (class "Default")
      (node (ref "OTHER") (pin "9") (pinfunction "9_9") (pintype "passive"))
      (node (ref "U0") (pin "33") (pinfunction "PB12_33") (pintype "bidirectional"))
    )
    (net (code "44") (name "/PC1") (class "Default")
      (node (ref "RED") (pin "2") (pinfunction "2_2") (pintype "passive"))
      (node (ref "U0") (pin "9") (pinfunction "PC1_9") (pintype "bidirectional"))
    )
    (net (code "45") (name "/PC2") (class "Default")
      (node (ref "OTHER") (pin "3") (pinfunction "3_3") (pintype "passive"))
      (node (ref "U0") (pin "10") (pinfunction "PC2_10") (pintype "bidirectional"))
    )
    (net (code "46") (name "/PC3") (class "Default")
      (node (ref "OTHER") (pin "5") (pinfunction "5_5") (pintype "passive"))
      (node (ref "U0") (pin "11") (pinfunction "PC3_11") (pintype "bidirectional"))
    )
    (net (code "47") (name "/PC4") (class "Default")
      (node (ref "TFT-LED") (pin "4") (pinfunction "4_4") (pintype "passive"))
      (node (ref "U0") (pin "24") (pinfunction "PC4_24") (pintype "bidirectional"))
    )
    (net (code "48") (name "/PC5") (class "Default")
      (node (ref "TFT-LED") (pin "2") (pinfunction "2_2") (pintype "passive"))
      (node (ref "U0") (pin "25") (pinfunction "PC5_25") (pintype "bidirectional"))
    )
    (net (code "49") (name "/PC9") (class "Default")
      (node (ref "OTHER") (pin "11") (pinfunction "11_11") (pintype "passive"))
      (node (ref "U0") (pin "40") (pinfunction "PC9_40") (pintype "bidirectional"))
    )
    (net (code "50") (name "/PC10") (class "Default")
      (node (ref "OTHER") (pin "6") (pinfunction "6_6") (pintype "passive"))
      (node (ref "U0") (pin "51") (pinfunction "PC10_51") (pintype "bidirectional"))
    )
    (net (code "51") (name "/PC11") (class "Default")
      (node (ref "OTHER") (pin "8") (pinfunction "8_8") (pintype "passive"))
      (node (ref "U0") (pin "52") (pinfunction "PC11_52") (pintype "bidirectional"))
    )
    (net (code "52") (name "/PC12") (class "Default")
      (node (ref "OTHER") (pin "10") (pinfunction "10_10") (pintype "passive"))
      (node (ref "U0") (pin "53") (pinfunction "PC12_53") (pintype "bidirectional"))
    )
    (net (code "53") (name "/PD2") (class "Default")
      (node (ref "OTHER") (pin "12") (pinfunction "12_12") (pintype "passive"))
      (node (ref "U0") (pin "54") (pinfunction "PD2_54") (pintype "bidirectional"))
    )
    (net (code "54") (name "/USB+") (class "Default")
      (node (ref "A0") (pin "3") (pinfunction "D+_3") (pintype "passive"))
      (node (ref "D+") (pin "1") (pinfunction "1_1") (pintype "passive"))
      (node (ref "U4") (pin "1") (pinfunction "UD+_1") (pintype "passive"))
    )
    (net (code "55") (name "/USB-") (class "Default")
      (node (ref "A0") (pin "2") (pinfunction "D_-_2") (pintype "passive"))
      (node (ref "D-") (pin "1") (pinfunction "1_1") (pintype "passive"))
      (node (ref "U4") (pin "2") (pinfunction "UD-_2") (pintype "passive"))
    )
    (net (code "56") (name "/VBAT") (class "Default")
      (node (ref "D1") (pin "2") (pinfunction "2_2") (pintype "passive"))
      (node (ref "D2") (pin "2") (pinfunction "2_2") (pintype "passive"))
      (node (ref "U0") (pin "1") (pinfunction "VBAT_1") (pintype "power_in"))
    )
    (net (code "57") (name "3V3") (class "Default")
      (node (ref "BEEP") (pin "1") (pinfunction "power+_1") (pintype "passive"))
      (node (ref "CC13") (pin "2") (pinfunction "2_2") (pintype "passive"))
      (node (ref "CC14") (pin "2") (pinfunction "2_2") (pintype "passive"))
      (node (ref "CC15") (pin "2") (pinfunction "2_2") (pintype "passive"))
      (node (ref "CC5") (pin "1") (pinfunction "1_1") (pintype "passive"))
      (node (ref "CC6") (pin "1") (pinfunction "1_1") (pintype "passive"))
      (node (ref "CC7") (pin "1") (pinfunction "1_1") (pintype "passive"))
      (node (ref "CC8") (pin "1") (pinfunction "1_1") (pintype "passive"))
      (node (ref "CC9") (pin "1") (pinfunction "1_1") (pintype "passive"))
      (node (ref "CR0") (pin "1") (pinfunction "1_1") (pintype "passive"))
      (node (ref "CR11") (pin "1") (pinfunction "1_1") (pintype "passive"))
      (node (ref "CR12") (pin "1") (pinfunction "1_1") (pintype "passive"))
      (node (ref "CR13") (pin "1") (pinfunction "1_1") (pintype "passive"))
      (node (ref "CR14") (pin "2") (pinfunction "2_2") (pintype "passive"))
      (node (ref "CR15") (pin "2") (pinfunction "2_2") (pintype "passive"))
      (node (ref "CR16") (pin "1") (pinfunction "1_1") (pintype "passive"))
      (node (ref "CR17") (pin "2") (pinfunction "2_2") (pintype "passive"))
      (node (ref "CR21") (pin "2") (pinfunction "2_2") (pintype "passive"))
      (node (ref "CR22") (pin "2") (pinfunction "2_2") (pintype "passive"))
      (node (ref "CR23") (pin "2") (pinfunction "2_2") (pintype "passive"))
      (node (ref "CR24") (pin "1") (pinfunction "1_1") (pintype "passive"))
      (node (ref "D1") (pin "1") (pinfunction "1_1") (pintype "passive"))
      (node (ref "D4") (pin "1") (pinfunction "1_1") (pintype "passive"))
      (node (ref "DEBUG") (pin "3") (pinfunction "3_3") (pintype "passive"))
      (node (ref "LED 2") (pin "1") (pinfunction "A_1") (pintype "passive"))
      (node (ref "LED 3") (pin "1") (pinfunction "A_1") (pintype "passive"))
      (node (ref "LED1") (pin "1") (pinfunction "A_1") (pintype "passive"))
      (node (ref "LED4") (pin "1") (pinfunction "A_1") (pintype "passive"))
      (node (ref "MOROT2") (pin "2") (pinfunction "2_2") (pintype "passive"))
      (node (ref "MPU6050") (pin "4") (pinfunction "4_4") (pintype "passive"))
      (node (ref "NRF2401") (pin "2") (pinfunction "2_2") (pintype "passive"))
      (node (ref "RED") (pin "3") (pinfunction "3_3") (pintype "passive"))
      (node (ref "SHT30") (pin "4") (pinfunction "4_4") (pintype "passive"))
      (node (ref "TEMT6000") (pin "1") (pinfunction "1_1") (pintype "passive"))
      (node (ref "TFT-LED") (pin "8") (pinfunction "8_8") (pintype "passive"))
      (node (ref "U0") (pin "13") (pinfunction "VDDA_13") (pintype "power_in"))
      (node (ref "U0") (pin "19") (pinfunction "VDD_4_19") (pintype "power_in"))
      (node (ref "U0") (pin "32") (pinfunction "VDD_1_32") (pintype "power_in"))
      (node (ref "U0") (pin "48") (pinfunction "VDD_2_48") (pintype "power_in"))
      (node (ref "U0") (pin "64") (pinfunction "VDD_3_64") (pintype "power_in"))
      (node (ref "UASM1") (pin "2") (pinfunction "OUT_2") (pintype "power_in"))
      (node (ref "XL53L0X") (pin "6") (pinfunction "6_6") (pintype "passive"))
    )
    (net (code "58") (name "5V_SYS") (class "Default")
      (node (ref "A0") (pin "1") (pinfunction "5V_1") (pintype "passive"))
      (node (ref "C19") (pin "1") (pinfunction "1_1") (pintype "passive"))
      (node (ref "C21") (pin "1") (pinfunction "1_1") (pintype "passive"))
      (node (ref "CC10") (pin "2") (pinfunction "2_2") (pintype "passive"))
      (node (ref "CC11") (pin "2") (pinfunction "2_2") (pintype "passive"))
      (node (ref "CC12") (pin "2") (pinfunction "2_2") (pintype "passive"))
      (node (ref "CC17") (pin "2") (pinfunction "2_2") (pintype "passive"))
      (node (ref "CHOOSE") (pin "1") (pinfunction "1_1") (pintype "passive"))
      (node (ref "D3") (pin "1") (pinfunction "1_1") (pintype "passive"))
      (node (ref "POWER") (pin "3") (pinfunction "3_3") (pintype "passive"))
      (node (ref "R29") (pin "1") (pinfunction "1_1") (pintype "passive"))
      (node (ref "R32") (pin "1") (pinfunction "1_1") (pintype "passive"))
      (node (ref "RASPI") (pin "2") (pinfunction "2_2") (pintype "passive"))
      (node (ref "U4") (pin "5") (pinfunction "VCC_5") (pintype "passive"))
      (node (ref "UASM1") (pin "3") (pinfunction "IN_3") (pintype "power_in"))
      (node (ref "uu1") (pin "7") (pinfunction "VOUT_7") (pintype "passive"))
      (node (ref "uu1") (pin "8") (pinfunction "VOUT_8") (pintype "passive"))
      (node (ref "uu2") (pin "7") (pinfunction "VOUT_7") (pintype "passive"))
      (node (ref "uu2") (pin "8") (pinfunction "VOUT_8") (pintype "passive"))
    )
    (net (code "59") (name "5V_motor") (class "Default")
      (node (ref "C23") (pin "1") (pinfunction "1_1") (pintype "passive"))
      (node (ref "C25") (pin "1") (pinfunction "1_1") (pintype "passive"))
      (node (ref "CHOOSE") (pin "2") (pinfunction "2_2") (pintype "passive"))
      (node (ref "LIGHT") (pin "2") (pinfunction "2_2") (pintype "passive"))
      (node (ref "MOROT2") (pin "1") (pinfunction "1_1") (pintype "passive"))
      (node (ref "POWER-F-O") (pin "2") (pinfunction "2_2") (pintype "passive"))
      (node (ref "R35") (pin "1") (pinfunction "1_1") (pintype "passive"))
      (node (ref "R38") (pin "1") (pinfunction "1_1") (pintype "passive"))
      (node (ref "U1") (pin "4") (pinfunction "VCC_4") (pintype "passive"))
      (node (ref "U2") (pin "4") (pinfunction "VCC_4") (pintype "passive"))
      (node (ref "uu3") (pin "7") (pinfunction "VOUT_7") (pintype "passive"))
      (node (ref "uu3") (pin "8") (pinfunction "VOUT_8") (pintype "passive"))
      (node (ref "uu4") (pin "7") (pinfunction "VOUT_7") (pintype "passive"))
      (node (ref "uu4") (pin "8") (pinfunction "VOUT_8") (pintype "passive"))
    )
    (net (code "60") (name "BAT") (class "Default")
      (node (ref "C18") (pin "1") (pinfunction "1_1") (pintype "passive"))
      (node (ref "C20") (pin "1") (pinfunction "1_1") (pintype "passive"))
      (node (ref "C22") (pin "1") (pinfunction "1_1") (pintype "passive"))
      (node (ref "C24") (pin "1") (pinfunction "1_1") (pintype "passive"))
      (node (ref "L1") (pin "1") (pinfunction "1_1") (pintype "passive"))
      (node (ref "L2") (pin "1") (pinfunction "1_1") (pintype "passive"))
      (node (ref "L3") (pin "1") (pinfunction "1_1") (pintype "passive"))
      (node (ref "L4") (pin "1") (pinfunction "1_1") (pintype "passive"))
      (node (ref "R28") (pin "1") (pinfunction "1_1") (pintype "passive"))
      (node (ref "R31") (pin "1") (pinfunction "1_1") (pintype "passive"))
      (node (ref "R34") (pin "1") (pinfunction "1_1") (pintype "passive"))
      (node (ref "R37") (pin "1") (pinfunction "1_1") (pintype "passive"))
      (node (ref "SW0") (pin "1") (pinfunction "1_1") (pintype "passive"))
      (node (ref "uu1") (pin "3") (pinfunction "VIN_3") (pintype "passive"))
      (node (ref "uu2") (pin "3") (pinfunction "VIN_3") (pintype "passive"))
      (node (ref "uu3") (pin "3") (pinfunction "VIN_3") (pintype "passive"))
      (node (ref "uu4") (pin "3") (pinfunction "VIN_3") (pintype "passive"))
    )
    (net (code "61") (name "GND") (class "Default")
      (node (ref "8MHz") (pin "3") (pinfunction "GND_3") (pintype "passive"))
      (node (ref "A0") (pin "5") (pinfunction "GND_5") (pintype "passive"))
      (node (ref "C16") (pin "1") (pinfunction "1_1") (pintype "passive"))
      (node (ref "C18") (pin "2") (pinfunction "2_2") (pintype "passive"))
      (node (ref "C19") (pin "2") (pinfunction "2_2") (pintype "passive"))
      (node (ref "C20") (pin "2") (pinfunction "2_2") (pintype "passive"))
      (node (ref "C21") (pin "2") (pinfunction "2_2") (pintype "passive"))
      (node (ref "C22") (pin "2") (pinfunction "2_2") (pintype "passive"))
      (node (ref "C23") (pin "2") (pinfunction "2_2") (pintype "passive"))
      (node (ref "C24") (pin "2") (pinfunction "2_2") (pintype "passive"))
      (node (ref "C25") (pin "2") (pinfunction "2_2") (pintype "passive"))
      (node (ref "CC0") (pin "1") (pinfunction "1_1") (pintype "passive"))
      (node (ref "CC1") (pin "1") (pinfunction "1_1") (pintype "passive"))
      (node (ref "CC10") (pin "1") (pinfunction "1_1") (pintype "passive"))
      (node (ref "CC11") (pin "1") (pinfunction "1_1") (pintype "passive"))
      (node (ref "CC12") (pin "1") (pinfunction "1_1") (pintype "passive"))
      (node (ref "CC13") (pin "1") (pinfunction "1_1") (pintype "passive"))
      (node (ref "CC14") (pin "1") (pinfunction "1_1") (pintype "passive"))
      (node (ref "CC15") (pin "1") (pinfunction "1_1") (pintype "passive"))
      (node (ref "CC17") (pin "1") (pinfunction "1_1") (pintype "passive"))
      (node (ref "CC2") (pin "1") (pinfunction "1_1") (pintype "passive"))
      (node (ref "CC3") (pin "1") (pinfunction "1_1") (pintype "passive"))
      (node (ref "CC4") (pin "1") (pinfunction "1_1") (pintype "passive"))
      (node (ref "CC5") (pin "2") (pinfunction "2_2") (pintype "passive"))
      (node (ref "CC6") (pin "2") (pinfunction "2_2") (pintype "passive"))
      (node (ref "CC7") (pin "2") (pinfunction "2_2") (pintype "passive"))
      (node (ref "CC8") (pin "2") (pinfunction "2_2") (pintype "passive"))
      (node (ref "CC9") (pin "2") (pinfunction "2_2") (pintype "passive"))
      (node (ref "CR1") (pin "2") (pinfunction "2_2") (pintype "passive"))
      (node (ref "CR10") (pin "1") (pinfunction "1_1") (pintype "passive"))
      (node (ref "CR2") (pin "1") (pinfunction "1_1") (pintype "passive"))
      (node (ref "CR4") (pin "2") (pinfunction "2_2") (pintype "passive"))
      (node (ref "CR7") (pin "2") (pinfunction "2_2") (pintype "passive"))
      (node (ref "CR8") (pin "2") (pinfunction "2_2") (pintype "passive"))
      (node (ref "CR9") (pin "1") (pinfunction "1_1") (pintype "passive"))
      (node (ref "D3") (pin "2") (pinfunction "2_2") (pintype "passive"))
      (node (ref "D4") (pin "2") (pinfunction "2_2") (pintype "passive"))
      (node (ref "DEBUG") (pin "4") (pinfunction "4_4") (pintype "passive"))
      (node (ref "K REST") (pin "1") (pinfunction "1_1") (pintype "passive"))
      (node (ref "MOROT2") (pin "6") (pinfunction "6_6") (pintype "passive"))
      (node (ref "MPU6050") (pin "1") (pinfunction "1_1") (pintype "passive"))
      (node (ref "NRF2401") (pin "1") (pinfunction "1_1") (pintype "passive"))
      (node (ref "POWER") (pin "1") (pinfunction "1_1") (pintype "passive"))
      (node (ref "POWER-F-O") (pin "1") (pinfunction "1_1") (pintype "passive"))
      (node (ref "R13") (pin "1") (pinfunction "1_1") (pintype "passive"))
      (node (ref "R25") (pin "1") (pinfunction "1_1") (pintype "passive"))
      (node (ref "R27") (pin "2") (pinfunction "2_2") (pintype "passive"))
      (node (ref "R30") (pin "2") (pinfunction "2_2") (pintype "passive"))
      (node (ref "R33") (pin "2") (pinfunction "2_2") (pintype "passive"))
      (node (ref "R36") (pin "2") (pinfunction "2_2") (pintype "passive"))
      (node (ref "R39") (pin "2") (pinfunction "2_2") (pintype "passive"))
      (node (ref "RASPI") (pin "1") (pinfunction "1_1") (pintype "passive"))
      (node (ref "RED") (pin "1") (pinfunction "1_1") (pintype "passive"))
      (node (ref "SHT30") (pin "3") (pinfunction "3_3") (pintype "passive"))
      (node (ref "TEMT6000") (pin "2") (pinfunction "2_2") (pintype "passive"))
      (node (ref "TFT-LED") (pin "7") (pinfunction "7_7") (pintype "passive"))
      (node (ref "U0") (pin "12") (pinfunction "VSSA_12") (pintype "power_in"))
      (node (ref "U0") (pin "18") (pinfunction "VSS_4_18") (pintype "power_in"))
      (node (ref "U0") (pin "31") (pinfunction "VSS_1_31") (pintype "power_in"))
      (node (ref "U0") (pin "47") (pinfunction "VSS_2_47") (pintype "power_in"))
      (node (ref "U0") (pin "63") (pinfunction "VSS_3_63") (pintype "power_in"))
      (node (ref "U1") (pin "3") (pinfunction "GND_3") (pintype "passive"))
      (node (ref "U2") (pin "3") (pinfunction "GND_3") (pintype "passive"))
      (node (ref "U3") (pin "2") (pinfunction "SOURCE_2") (pintype "passive"))
      (node (ref "U4") (pin "3") (pinfunction "GND_3") (pintype "passive"))
      (node (ref "U5") (pin "2") (pinfunction "SOURCE_2") (pintype "passive"))
      (node (ref "UASM1") (pin "1") (pinfunction "GND_1") (pintype "power_in"))
      (node (ref "XL53L0X") (pin "5") (pinfunction "5_5") (pintype "passive"))
      (node (ref "buttery") (pin "2") (pinfunction "2_2") (pintype "passive"))
      (node (ref "uu1") (pin "5") (pinfunction "GND_5") (pintype "passive"))
      (node (ref "uu2") (pin "5") (pinfunction "GND_5") (pintype "passive"))
      (node (ref "uu3") (pin "5") (pinfunction "GND_5") (pintype "passive"))
      (node (ref "uu4") (pin "5") (pinfunction "GND_5") (pintype "passive"))
    )
    (net (code "62") (name "Net-(BEEP-power-)") (class "Default")
      (node (ref "BEEP") (pin "2") (pinfunction "power-_2") (pintype "passive"))
      (node (ref "U3") (pin "3") (pinfunction "DRAIN_3") (pintype "passive"))
    )
    (net (code "63") (name "Net-(CR20-Pad1)") (class "Default")
      (node (ref "CR20") (pin "1") (pinfunction "1_1") (pintype "passive"))
      (node (ref "NRF2401") (pin "8") (pinfunction "8_8") (pintype "passive"))
    )
    (net (code "64") (name "Net-(D2-Pad1)") (class "Default")
      (node (ref "D2") (pin "1") (pinfunction "1_1") (pintype "passive"))
      (node (ref "buttery") (pin "1") (pinfunction "1_1") (pintype "passive"))
    )
    (net (code "65") (name "Net-(L1-Pad2)") (class "Default")
      (node (ref "L1") (pin "2") (pinfunction "2_2") (pintype "passive"))
      (node (ref "uu1") (pin "1") (pinfunction "SW_1") (pintype "passive"))
      (node (ref "uu1") (pin "2") (pinfunction "SW_2") (pintype "passive"))
    )
    (net (code "66") (name "Net-(L2-Pad2)") (class "Default")
      (node (ref "L2") (pin "2") (pinfunction "2_2") (pintype "passive"))
      (node (ref "uu2") (pin "1") (pinfunction "SW_1") (pintype "passive"))
      (node (ref "uu2") (pin "2") (pinfunction "SW_2") (pintype "passive"))
    )
    (net (code "67") (name "Net-(L3-Pad2)") (class "Default")
      (node (ref "L3") (pin "2") (pinfunction "2_2") (pintype "passive"))
      (node (ref "uu3") (pin "1") (pinfunction "SW_1") (pintype "passive"))
      (node (ref "uu3") (pin "2") (pinfunction "SW_2") (pintype "passive"))
    )
    (net (code "68") (name "Net-(L4-Pad2)") (class "Default")
      (node (ref "L4") (pin "2") (pinfunction "2_2") (pintype "passive"))
      (node (ref "uu4") (pin "1") (pinfunction "SW_1") (pintype "passive"))
      (node (ref "uu4") (pin "2") (pinfunction "SW_2") (pintype "passive"))
    )
    (net (code "69") (name "Net-(LED 2-K)") (class "Default")
      (node (ref "CR4") (pin "1") (pinfunction "1_1") (pintype "passive"))
      (node (ref "LED 2") (pin "2") (pinfunction "K_2") (pintype "passive"))
    )
    (net (code "70") (name "Net-(LED 3-K)") (class "Default")
      (node (ref "CR6") (pin "1") (pinfunction "1_1") (pintype "passive"))
      (node (ref "LED 3") (pin "2") (pinfunction "K_2") (pintype "passive"))
    )
    (net (code "71") (name "Net-(LED1-K)") (class "Default")
      (node (ref "CR3") (pin "1") (pinfunction "1_1") (pintype "passive"))
      (node (ref "LED1") (pin "2") (pinfunction "K_2") (pintype "passive"))
    )
    (net (code "72") (name "Net-(LED4-K)") (class "Default")
      (node (ref "CR5") (pin "1") (pinfunction "1_1") (pintype "passive"))
      (node (ref "LED4") (pin "2") (pinfunction "K_2") (pintype "passive"))
    )
    (net (code "73") (name "Net-(MOTOR-Pad1)") (class "Default")
      (node (ref "MOTOR") (pin "1") (pinfunction "1_1") (pintype "passive"))
      (node (ref "U1") (pin "5") (pinfunction "FO_5") (pintype "passive"))
      (node (ref "U1") (pin "6") (pinfunction "FO_6") (pintype "passive"))
    )
    (net (code "74") (name "Net-(MOTOR-Pad2)") (class "Default")
      (node (ref "MOTOR") (pin "2") (pinfunction "2_2") (pintype "passive"))
      (node (ref "U1") (pin "7") (pinfunction "BO_7") (pintype "passive"))
      (node (ref "U1") (pin "8") (pinfunction "BO_8") (pintype "passive"))
    )
    (net (code "75") (name "Net-(MOTOR-Pad3)") (class "Default")
      (node (ref "MOTOR") (pin "3") (pinfunction "3_3") (pintype "passive"))
      (node (ref "U2") (pin "5") (pinfunction "FO_5") (pintype "passive"))
      (node (ref "U2") (pin "6") (pinfunction "FO_6") (pintype "passive"))
    )
    (net (code "76") (name "Net-(MOTOR-Pad4)") (class "Default")
      (node (ref "MOTOR") (pin "4") (pinfunction "4_4") (pintype "passive"))
      (node (ref "U2") (pin "7") (pinfunction "BO_7") (pintype "passive"))
      (node (ref "U2") (pin "8") (pinfunction "BO_8") (pintype "passive"))
    )
    (net (code "77") (name "Net-(POWER-Pad2)") (class "Default")
      (node (ref "POWER") (pin "2") (pinfunction "2_2") (pintype "passive"))
      (node (ref "R26") (pin "2") (pinfunction "2_2") (pintype "passive"))
      (node (ref "SW0") (pin "2") (pinfunction "2_2") (pintype "passive"))
    )
    (net (code "78") (name "Net-(U4-RXD)") (class "Default")
      (node (ref "D5") (pin "1") (pinfunction "1_1") (pintype "passive"))
      (node (ref "U4") (pin "7") (pinfunction "RXD_7") (pintype "passive"))
    )
    (net (code "79") (name "Net-(U4-TXD)") (class "Default")
      (node (ref "D6") (pin "2") (pinfunction "2_2") (pintype "passive"))
      (node (ref "U4") (pin "6") (pinfunction "TXD_6") (pintype "passive"))
    )
    (net (code "80") (name "Net-(U4-V3)") (class "Default")
      (node (ref "C16") (pin "2") (pinfunction "2_2") (pintype "passive"))
      (node (ref "U4") (pin "8") (pinfunction "V3_8") (pintype "passive"))
    )
    (net (code "81") (name "Net-(U5-DRAIN)") (class "Default")
      (node (ref "LIGHT") (pin "1") (pinfunction "1_1") (pintype "passive"))
      (node (ref "U5") (pin "3") (pinfunction "DRAIN_3") (pintype "passive"))
    )
    (net (code "82") (name "Net-(uu1-EV)") (class "Default")
      (node (ref "R28") (pin "2") (pinfunction "2_2") (pintype "passive"))
      (node (ref "uu1") (pin "4") (pinfunction "EV_4") (pintype "passive"))
    )
    (net (code "83") (name "Net-(uu1-FB)") (class "Default")
      (node (ref "R29") (pin "2") (pinfunction "2_2") (pintype "passive"))
      (node (ref "R30") (pin "1") (pinfunction "1_1") (pintype "passive"))
      (node (ref "uu1") (pin "6") (pinfunction "FB_6") (pintype "passive"))
    )
    (net (code "84") (name "Net-(uu2-EV)") (class "Default")
      (node (ref "R31") (pin "2") (pinfunction "2_2") (pintype "passive"))
      (node (ref "uu2") (pin "4") (pinfunction "EV_4") (pintype "passive"))
    )
    (net (code "85") (name "Net-(uu2-FB)") (class "Default")
      (node (ref "R32") (pin "2") (pinfunction "2_2") (pintype "passive"))
      (node (ref "R33") (pin "1") (pinfunction "1_1") (pintype "passive"))
      (node (ref "uu2") (pin "6") (pinfunction "FB_6") (pintype "passive"))
    )
    (net (code "86") (name "Net-(uu3-EV)") (class "Default")
      (node (ref "R34") (pin "2") (pinfunction "2_2") (pintype "passive"))
      (node (ref "uu3") (pin "4") (pinfunction "EV_4") (pintype "passive"))
    )
    (net (code "87") (name "Net-(uu3-FB)") (class "Default")
      (node (ref "R35") (pin "2") (pinfunction "2_2") (pintype "passive"))
      (node (ref "R36") (pin "1") (pinfunction "1_1") (pintype "passive"))
      (node (ref "uu3") (pin "6") (pinfunction "FB_6") (pintype "passive"))
    )
    (net (code "88") (name "Net-(uu4-EV)") (class "Default")
      (node (ref "R37") (pin "2") (pinfunction "2_2") (pintype "passive"))
      (node (ref "uu4") (pin "4") (pinfunction "EV_4") (pintype "passive"))
    )
    (net (code "89") (name "Net-(uu4-FB)") (class "Default")
      (node (ref "R38") (pin "2") (pinfunction "2_2") (pintype "passive"))
      (node (ref "R39") (pin "1") (pinfunction "1_1") (pintype "passive"))
      (node (ref "uu4") (pin "6") (pinfunction "FB_6") (pintype "passive"))
    )
    (net (code "90") (name "unconnected-(A0-ID-Pad4)") (class "Default")
      (node (ref "A0") (pin "4") (pinfunction "ID_4") (pintype "passive+no_connect"))
    )
    (net (code "91") (name "unconnected-(A0-Pad6)") (class "Default")
      (node (ref "A0") (pin "6") (pinfunction "6_6") (pintype "passive+no_connect"))
    )
    (net (code "92") (name "unconnected-(A0-Pad7)") (class "Default")
      (node (ref "A0") (pin "7") (pinfunction "7_7") (pintype "passive+no_connect"))
    )
    (net (code "93") (name "unconnected-(A0-Pad8)") (class "Default")
      (node (ref "A0") (pin "8") (pinfunction "8_8") (pintype "passive+no_connect"))
    )
    (net (code "94") (name "unconnected-(A0-Pad9)") (class "Default")
      (node (ref "A0") (pin "9") (pinfunction "9_9") (pintype "passive+no_connect"))
    )
    (net (code "95") (name "unconnected-(MOROT2-Pad5)") (class "Default")
      (node (ref "MOROT2") (pin "5") (pinfunction "5_5") (pintype "passive+no_connect"))
    )
    (net (code "96") (name "unconnected-(SW0-Pad3)") (class "Default")
      (node (ref "SW0") (pin "3") (pinfunction "3_3") (pintype "passive+no_connect"))
    )
    (net (code "97") (name "unconnected-(U4-RTS#-Pad4)") (class "Default")
      (node (ref "U4") (pin "4") (pinfunction "RTS#_4") (pintype "passive+no_connect"))
    )
  )
)
